# 4-Microcontroller.net
KiCad netlist of a schematic drawn in Altium Designer
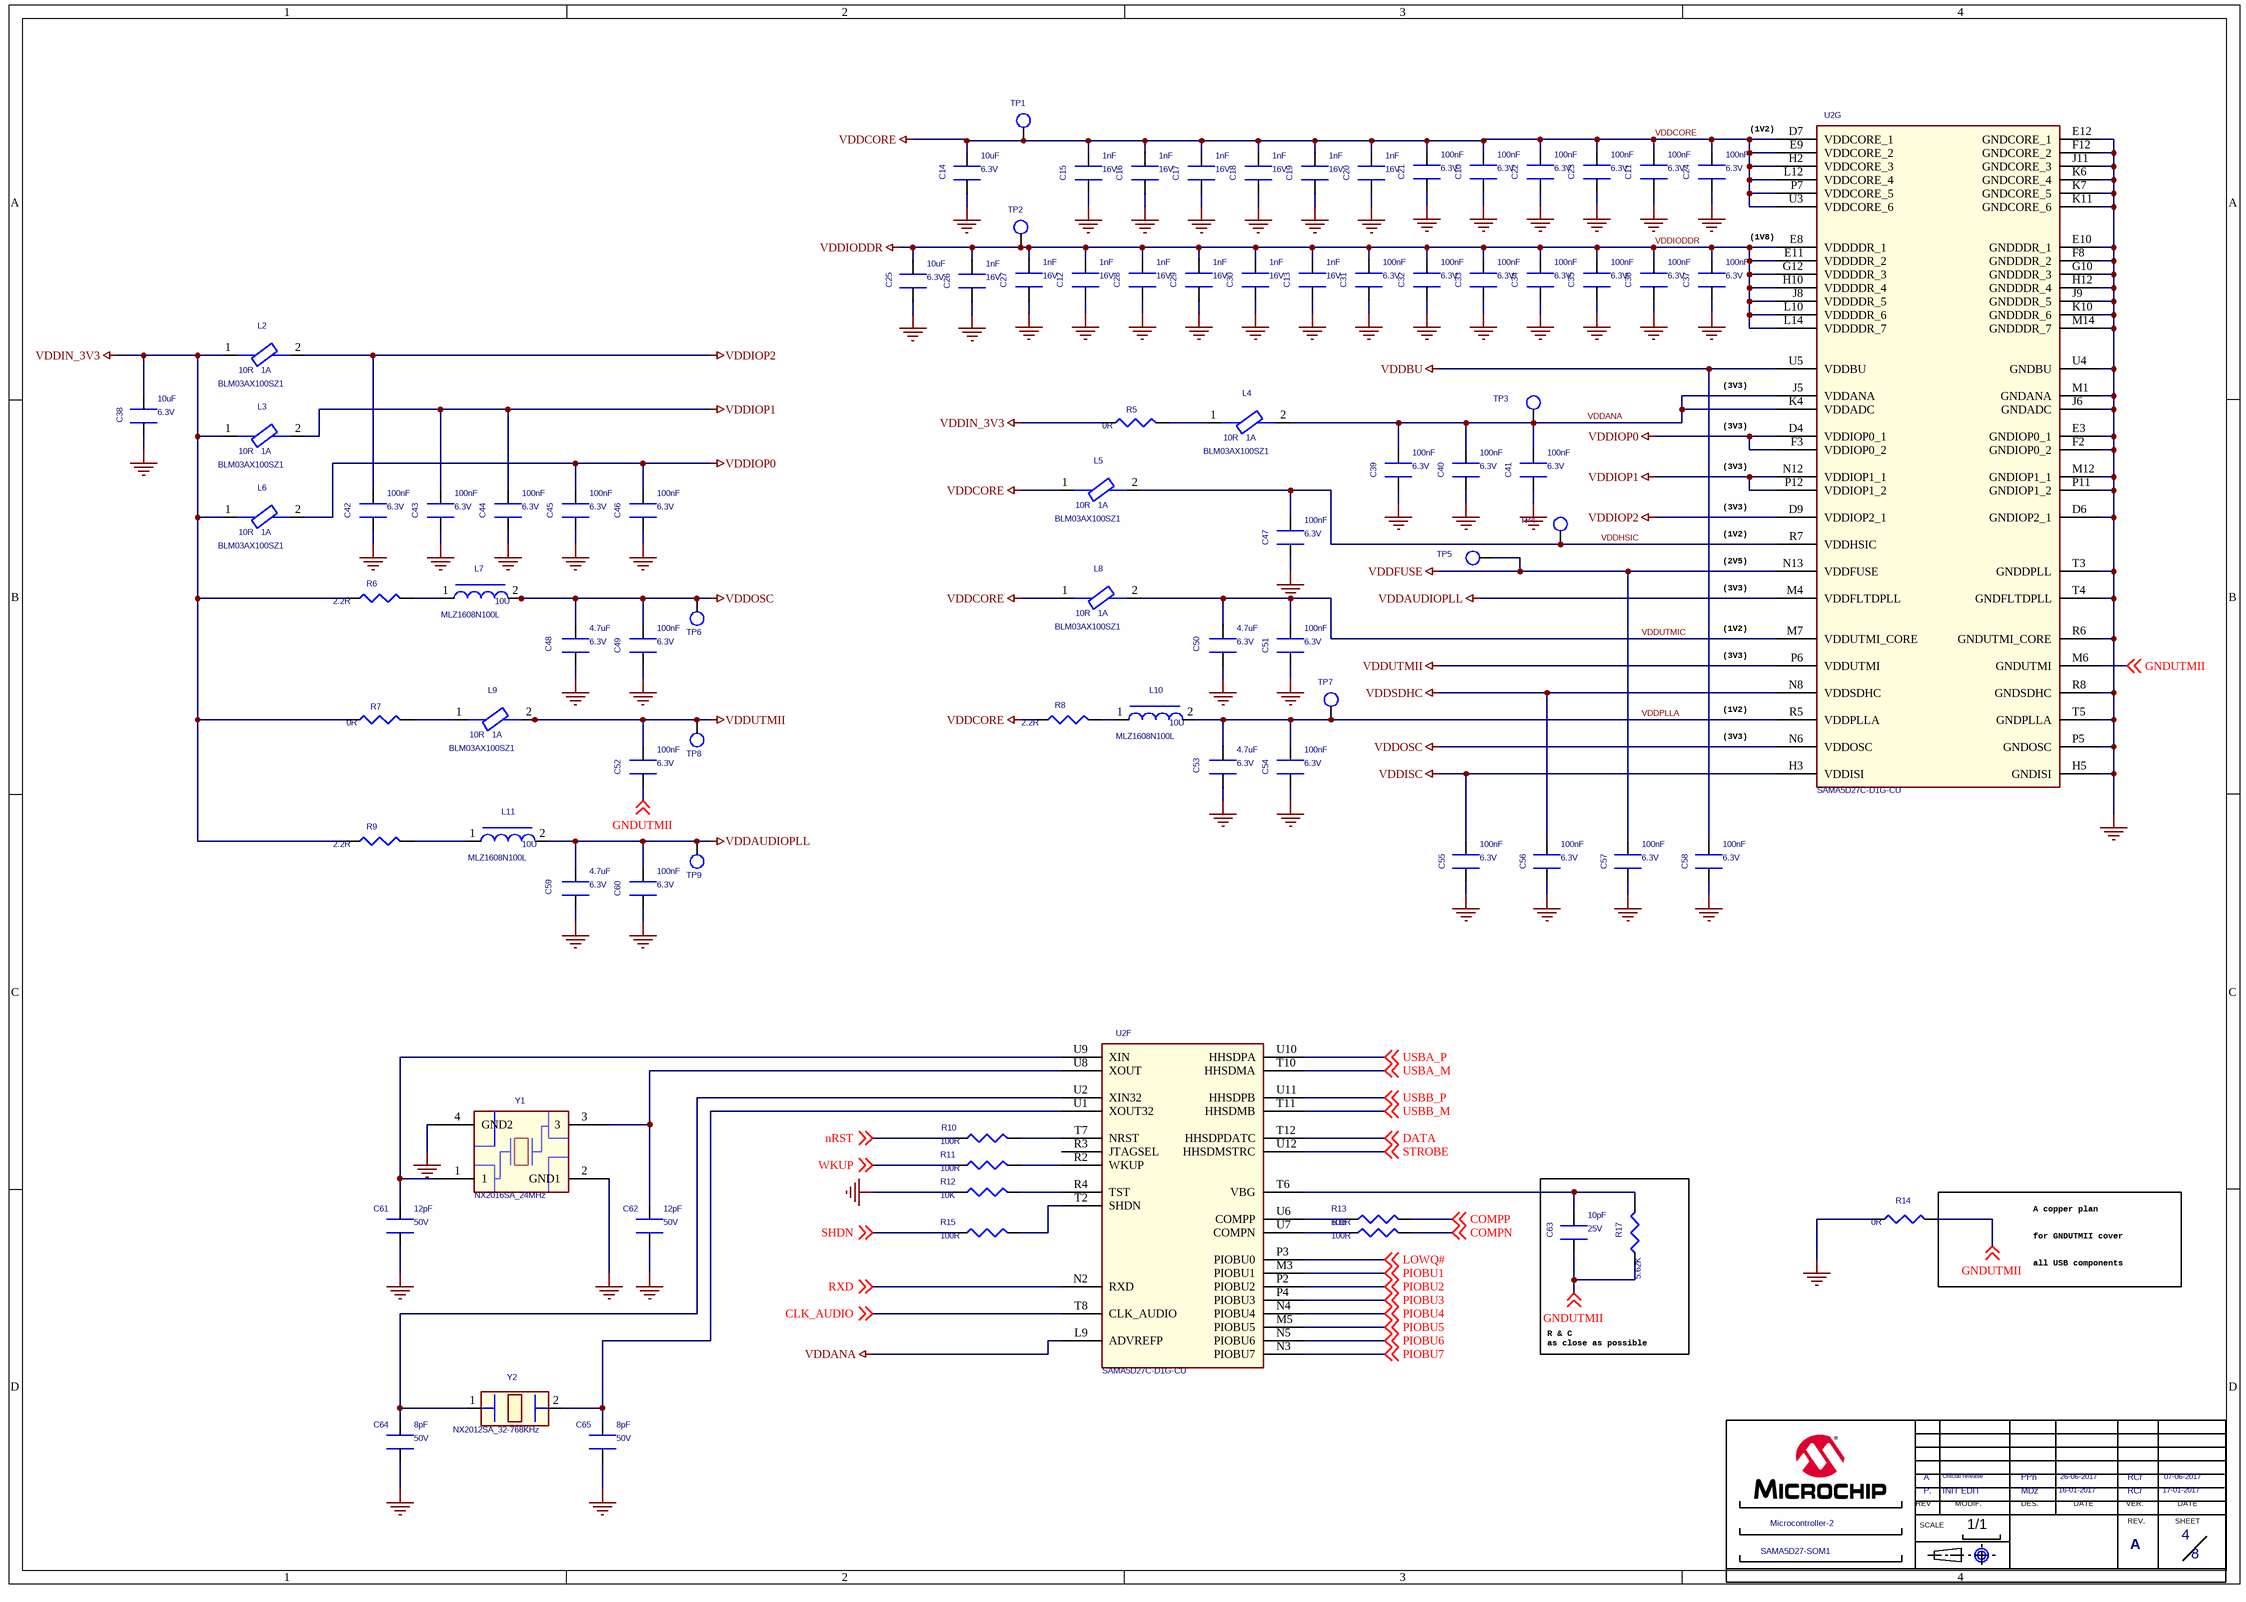
[diagram p0: 4-Microcontroller.SchDoc]

(export (version "E")
  (design (tool "Eeschema 10.0.6"))
  (components
    (comp (ref "C10")
      (value "xpF x% xV")
      (footprint "C0201")
      (fields (field (name "VALEUR") "100nF") (field (name "TENSION") "6.3V") (field (name "HAUTEUR") "xmm"))
      (libsource (lib "*") (part "C0201-100nF-X5R-6.3V"))
    )
    (comp (ref "C11")
      (value "xpF x% xV")
      (footprint "C0201")
      (fields (field (name "VALEUR") "100nF") (field (name "TENSION") "6.3V") (field (name "HAUTEUR") "xmm"))
      (libsource (lib "*") (part "C0201-100nF-X5R-6.3V"))
    )
    (comp (ref "C12")
      (value "xpF x% xV")
      (footprint "C0201")
      (fields (field (name "TENSION") "16V") (field (name "VALEUR") "1nF") (field (name "HAUTEUR") "xmm"))
      (libsource (lib "*") (part "C0201-1nF-X7R-16V-10%"))
    )
    (comp (ref "C13")
      (value "xpF x% xV")
      (footprint "C0201")
      (fields (field (name "TENSION") "16V") (field (name "VALEUR") "1nF") (field (name "HAUTEUR") "xmm"))
      (libsource (lib "*") (part "C0201-1nF-X7R-16V-10%"))
    )
    (comp (ref "C14")
      (value "xpF x% xV")
      (footprint "C0402")
      (fields (field (name "TENSION") "6.3V") (field (name "VALEUR") "10uF") (field (name "HAUTEUR") "xmm"))
      (libsource (lib "*") (part "C0402-10uF-X5R-6.3V"))
    )
    (comp (ref "C15")
      (value "xpF x% xV")
      (footprint "C0201")
      (fields (field (name "TENSION") "16V") (field (name "VALEUR") "1nF") (field (name "HAUTEUR") "xmm"))
      (libsource (lib "*") (part "C0201-1nF-X7R-16V-10%"))
    )
    (comp (ref "C16")
      (value "xpF x% xV")
      (footprint "C0201")
      (fields (field (name "TENSION") "16V") (field (name "VALEUR") "1nF") (field (name "HAUTEUR") "xmm"))
      (libsource (lib "*") (part "C0201-1nF-X7R-16V-10%"))
    )
    (comp (ref "C17")
      (value "xpF x% xV")
      (footprint "C0201")
      (fields (field (name "TENSION") "16V") (field (name "VALEUR") "1nF") (field (name "HAUTEUR") "xmm"))
      (libsource (lib "*") (part "C0201-1nF-X7R-16V-10%"))
    )
    (comp (ref "C18")
      (value "xpF x% xV")
      (footprint "C0201")
      (fields (field (name "TENSION") "16V") (field (name "VALEUR") "1nF") (field (name "HAUTEUR") "xmm"))
      (libsource (lib "*") (part "C0201-1nF-X7R-16V-10%"))
    )
    (comp (ref "C19")
      (value "xpF x% xV")
      (footprint "C0201")
      (fields (field (name "TENSION") "16V") (field (name "VALEUR") "1nF") (field (name "HAUTEUR") "xmm"))
      (libsource (lib "*") (part "C0201-1nF-X7R-16V-10%"))
    )
    (comp (ref "C20")
      (value "xpF x% xV")
      (footprint "C0201")
      (fields (field (name "TENSION") "16V") (field (name "VALEUR") "1nF") (field (name "HAUTEUR") "xmm"))
      (libsource (lib "*") (part "C0201-1nF-X7R-16V-10%"))
    )
    (comp (ref "C21")
      (value "xpF x% xV")
      (footprint "C0201")
      (fields (field (name "VALEUR") "100nF") (field (name "TENSION") "6.3V") (field (name "HAUTEUR") "xmm"))
      (libsource (lib "*") (part "C0201-100nF-X5R-6.3V"))
    )
    (comp (ref "C22")
      (value "xpF x% xV")
      (footprint "C0201")
      (fields (field (name "VALEUR") "100nF") (field (name "TENSION") "6.3V") (field (name "HAUTEUR") "xmm"))
      (libsource (lib "*") (part "C0201-100nF-X5R-6.3V"))
    )
    (comp (ref "C23")
      (value "xpF x% xV")
      (footprint "C0201")
      (fields (field (name "VALEUR") "100nF") (field (name "TENSION") "6.3V") (field (name "HAUTEUR") "xmm"))
      (libsource (lib "*") (part "C0201-100nF-X5R-6.3V"))
    )
    (comp (ref "C24")
      (value "xpF x% xV")
      (footprint "C0201")
      (fields (field (name "VALEUR") "100nF") (field (name "TENSION") "6.3V") (field (name "HAUTEUR") "xmm"))
      (libsource (lib "*") (part "C0201-100nF-X5R-6.3V"))
    )
    (comp (ref "C25")
      (value "xpF x% xV")
      (footprint "C0402")
      (fields (field (name "TENSION") "6.3V") (field (name "VALEUR") "10uF") (field (name "HAUTEUR") "xmm"))
      (libsource (lib "*") (part "C0402-10uF-X5R-6.3V"))
    )
    (comp (ref "C26")
      (value "xpF x% xV")
      (footprint "C0201")
      (fields (field (name "TENSION") "16V") (field (name "VALEUR") "1nF") (field (name "HAUTEUR") "xmm"))
      (libsource (lib "*") (part "C0201-1nF-X7R-16V-10%"))
    )
    (comp (ref "C27")
      (value "xpF x% xV")
      (footprint "C0201")
      (fields (field (name "TENSION") "16V") (field (name "VALEUR") "1nF") (field (name "HAUTEUR") "xmm"))
      (libsource (lib "*") (part "C0201-1nF-X7R-16V-10%"))
    )
    (comp (ref "C28")
      (value "xpF x% xV")
      (footprint "C0201")
      (fields (field (name "TENSION") "16V") (field (name "VALEUR") "1nF") (field (name "HAUTEUR") "xmm"))
      (libsource (lib "*") (part "C0201-1nF-X7R-16V-10%"))
    )
    (comp (ref "C29")
      (value "xpF x% xV")
      (footprint "C0201")
      (fields (field (name "TENSION") "16V") (field (name "VALEUR") "1nF") (field (name "HAUTEUR") "xmm"))
      (libsource (lib "*") (part "C0201-1nF-X7R-16V-10%"))
    )
    (comp (ref "C30")
      (value "xpF x% xV")
      (footprint "C0201")
      (fields (field (name "TENSION") "16V") (field (name "VALEUR") "1nF") (field (name "HAUTEUR") "xmm"))
      (libsource (lib "*") (part "C0201-1nF-X7R-16V-10%"))
    )
    (comp (ref "C31")
      (value "xpF x% xV")
      (footprint "C0201")
      (fields (field (name "VALEUR") "100nF") (field (name "TENSION") "6.3V") (field (name "HAUTEUR") "xmm"))
      (libsource (lib "*") (part "C0201-100nF-X5R-6.3V"))
    )
    (comp (ref "C32")
      (value "xpF x% xV")
      (footprint "C0201")
      (fields (field (name "VALEUR") "100nF") (field (name "TENSION") "6.3V") (field (name "HAUTEUR") "xmm"))
      (libsource (lib "*") (part "C0201-100nF-X5R-6.3V"))
    )
    (comp (ref "C33")
      (value "xpF x% xV")
      (footprint "C0201")
      (fields (field (name "VALEUR") "100nF") (field (name "TENSION") "6.3V") (field (name "HAUTEUR") "xmm"))
      (libsource (lib "*") (part "C0201-100nF-X5R-6.3V"))
    )
    (comp (ref "C34")
      (value "xpF x% xV")
      (footprint "C0201")
      (fields (field (name "VALEUR") "100nF") (field (name "TENSION") "6.3V") (field (name "HAUTEUR") "xmm"))
      (libsource (lib "*") (part "C0201-100nF-X5R-6.3V"))
    )
    (comp (ref "C35")
      (value "xpF x% xV")
      (footprint "C0201")
      (fields (field (name "VALEUR") "100nF") (field (name "TENSION") "6.3V") (field (name "HAUTEUR") "xmm"))
      (libsource (lib "*") (part "C0201-100nF-X5R-6.3V"))
    )
    (comp (ref "C36")
      (value "xpF x% xV")
      (footprint "C0201")
      (fields (field (name "VALEUR") "100nF") (field (name "TENSION") "6.3V") (field (name "HAUTEUR") "xmm"))
      (libsource (lib "*") (part "C0201-100nF-X5R-6.3V"))
    )
    (comp (ref "C37")
      (value "xpF x% xV")
      (footprint "C0201")
      (fields (field (name "VALEUR") "100nF") (field (name "TENSION") "6.3V") (field (name "HAUTEUR") "xmm"))
      (libsource (lib "*") (part "C0201-100nF-X5R-6.3V"))
    )
    (comp (ref "C38")
      (value "xpF x% xV")
      (footprint "C0402")
      (fields (field (name "TENSION") "6.3V") (field (name "VALEUR") "10uF") (field (name "HAUTEUR") "xmm"))
      (libsource (lib "*") (part "C0402-10uF-X5R-6.3V"))
    )
    (comp (ref "C39")
      (value "xpF x% xV")
      (footprint "C0201")
      (fields (field (name "VALEUR") "100nF") (field (name "TENSION") "6.3V") (field (name "HAUTEUR") "xmm"))
      (libsource (lib "*") (part "C0201-100nF-X5R-6.3V"))
    )
    (comp (ref "C40")
      (value "xpF x% xV")
      (footprint "C0201")
      (fields (field (name "VALEUR") "100nF") (field (name "TENSION") "6.3V") (field (name "HAUTEUR") "xmm"))
      (libsource (lib "*") (part "C0201-100nF-X5R-6.3V"))
    )
    (comp (ref "C41")
      (value "xpF x% xV")
      (footprint "C0201")
      (fields (field (name "VALEUR") "100nF") (field (name "TENSION") "6.3V") (field (name "HAUTEUR") "xmm"))
      (libsource (lib "*") (part "C0201-100nF-X5R-6.3V"))
    )
    (comp (ref "C42")
      (value "xpF x% xV")
      (footprint "C0201")
      (fields (field (name "VALEUR") "100nF") (field (name "TENSION") "6.3V") (field (name "HAUTEUR") "xmm"))
      (libsource (lib "*") (part "C0201-100nF-X5R-6.3V"))
    )
    (comp (ref "C43")
      (value "xpF x% xV")
      (footprint "C0201")
      (fields (field (name "VALEUR") "100nF") (field (name "TENSION") "6.3V") (field (name "HAUTEUR") "xmm"))
      (libsource (lib "*") (part "C0201-100nF-X5R-6.3V"))
    )
    (comp (ref "C44")
      (value "xpF x% xV")
      (footprint "C0201")
      (fields (field (name "VALEUR") "100nF") (field (name "TENSION") "6.3V") (field (name "HAUTEUR") "xmm"))
      (libsource (lib "*") (part "C0201-100nF-X5R-6.3V"))
    )
    (comp (ref "C45")
      (value "xpF x% xV")
      (footprint "C0201")
      (fields (field (name "VALEUR") "100nF") (field (name "TENSION") "6.3V") (field (name "HAUTEUR") "xmm"))
      (libsource (lib "*") (part "C0201-100nF-X5R-6.3V"))
    )
    (comp (ref "C46")
      (value "xpF x% xV")
      (footprint "C0201")
      (fields (field (name "VALEUR") "100nF") (field (name "TENSION") "6.3V") (field (name "HAUTEUR") "xmm"))
      (libsource (lib "*") (part "C0201-100nF-X5R-6.3V"))
    )
    (comp (ref "C47")
      (value "xpF x% xV")
      (footprint "C0201")
      (fields (field (name "VALEUR") "100nF") (field (name "TENSION") "6.3V") (field (name "HAUTEUR") "xmm"))
      (libsource (lib "*") (part "C0201-100nF-X5R-6.3V"))
    )
    (comp (ref "C48")
      (value "xpF x% xV")
      (footprint "C0402")
      (fields (field (name "TENSION") "6.3V") (field (name "VALEUR") "4.7uF") (field (name "HAUTEUR") "xmm"))
      (libsource (lib "*") (part "C0402-4.7uF-X5R-6.3V-10%"))
    )
    (comp (ref "C49")
      (value "xpF x% xV")
      (footprint "C0201")
      (fields (field (name "VALEUR") "100nF") (field (name "TENSION") "6.3V") (field (name "HAUTEUR") "xmm"))
      (libsource (lib "*") (part "C0201-100nF-X5R-6.3V"))
    )
    (comp (ref "C50")
      (value "xpF x% xV")
      (footprint "C0402")
      (fields (field (name "TENSION") "6.3V") (field (name "VALEUR") "4.7uF") (field (name "HAUTEUR") "xmm"))
      (libsource (lib "*") (part "C0402-4.7uF-X5R-6.3V-10%"))
    )
    (comp (ref "C51")
      (value "xpF x% xV")
      (footprint "C0201")
      (fields (field (name "VALEUR") "100nF") (field (name "TENSION") "6.3V") (field (name "HAUTEUR") "xmm"))
      (libsource (lib "*") (part "C0201-100nF-X5R-6.3V"))
    )
    (comp (ref "C52")
      (value "xpF x% xV")
      (footprint "C0201")
      (fields (field (name "VALEUR") "100nF") (field (name "TENSION") "6.3V") (field (name "HAUTEUR") "xmm"))
      (libsource (lib "*") (part "C0201-100nF-X5R-6.3V"))
    )
    (comp (ref "C53")
      (value "xpF x% xV")
      (footprint "C0402")
      (fields (field (name "TENSION") "6.3V") (field (name "VALEUR") "4.7uF") (field (name "HAUTEUR") "xmm"))
      (libsource (lib "*") (part "C0402-4.7uF-X5R-6.3V-10%"))
    )
    (comp (ref "C54")
      (value "xpF x% xV")
      (footprint "C0201")
      (fields (field (name "VALEUR") "100nF") (field (name "TENSION") "6.3V") (field (name "HAUTEUR") "xmm"))
      (libsource (lib "*") (part "C0201-100nF-X5R-6.3V"))
    )
    (comp (ref "C55")
      (value "xpF x% xV")
      (footprint "C0201")
      (fields (field (name "VALEUR") "100nF") (field (name "TENSION") "6.3V") (field (name "HAUTEUR") "xmm"))
      (libsource (lib "*") (part "C0201-100nF-X5R-6.3V"))
    )
    (comp (ref "C56")
      (value "xpF x% xV")
      (footprint "C0201")
      (fields (field (name "VALEUR") "100nF") (field (name "TENSION") "6.3V") (field (name "HAUTEUR") "xmm"))
      (libsource (lib "*") (part "C0201-100nF-X5R-6.3V"))
    )
    (comp (ref "C57")
      (value "xpF x% xV")
      (footprint "C0201")
      (fields (field (name "VALEUR") "100nF") (field (name "TENSION") "6.3V") (field (name "HAUTEUR") "xmm"))
      (libsource (lib "*") (part "C0201-100nF-X5R-6.3V"))
    )
    (comp (ref "C58")
      (value "xpF x% xV")
      (footprint "C0201")
      (fields (field (name "VALEUR") "100nF") (field (name "TENSION") "6.3V") (field (name "HAUTEUR") "xmm"))
      (libsource (lib "*") (part "C0201-100nF-X5R-6.3V"))
    )
    (comp (ref "C59")
      (value "xpF x% xV")
      (footprint "C0402")
      (fields (field (name "TENSION") "6.3V") (field (name "VALEUR") "4.7uF") (field (name "HAUTEUR") "xmm"))
      (libsource (lib "*") (part "C0402-4.7uF-X5R-6.3V-10%"))
    )
    (comp (ref "C60")
      (value "xpF x% xV")
      (footprint "C0201")
      (fields (field (name "VALEUR") "100nF") (field (name "TENSION") "6.3V") (field (name "HAUTEUR") "xmm"))
      (libsource (lib "*") (part "C0201-100nF-X5R-6.3V"))
    )
    (comp (ref "C61")
      (value "xpF x% xV")
      (footprint "C0201")
      (fields (field (name "TENSION") "50V") (field (name "VALEUR") "12pF") (field (name "HAUTEUR") "xmm"))
      (libsource (lib "*") (part "C0201-12pF-C0G-50V"))
    )
    (comp (ref "C62")
      (value "xpF x% xV")
      (footprint "C0201")
      (fields (field (name "TENSION") "50V") (field (name "VALEUR") "12pF") (field (name "HAUTEUR") "xmm"))
      (libsource (lib "*") (part "C0201-12pF-C0G-50V"))
    )
    (comp (ref "C63")
      (value "xpF x% xV")
      (footprint "C0201")
      (fields (field (name "VALEUR") "10pF") (field (name "TENSION") "25V") (field (name "HAUTEUR") "xmm"))
      (libsource (lib "*") (part "C0201-10pF-C0G-25V"))
    )
    (comp (ref "C64")
      (value "xpF x% xV")
      (footprint "C0201")
      (fields (field (name "VALEUR") "8pF") (field (name "TENSION") "50V") (field (name "HAUTEUR") "xmm"))
      (libsource (lib "*") (part "C0201-8pF-C0G-50V"))
    )
    (comp (ref "C65")
      (value "xpF x% xV")
      (footprint "C0201")
      (fields (field (name "VALEUR") "8pF") (field (name "TENSION") "50V") (field (name "HAUTEUR") "xmm"))
      (libsource (lib "*") (part "C0201-8pF-C0G-50V"))
    )
    (comp (ref "L2")
      (value "10R   1A")
      (footprint "L0201")
      (fields
        (field (name "VALEUR") "BLM03AX100SZ1")
        (field (name "PARTNUMBER") "BLM03AX100SZ1")
        (field (name "TOLERANCE") "20%")
      )
      (libsource (lib "*") (part "BLM03AX100SZ1"))
    )
    (comp (ref "L3")
      (value "10R   1A")
      (footprint "L0201")
      (fields
        (field (name "VALEUR") "BLM03AX100SZ1")
        (field (name "PARTNUMBER") "BLM03AX100SZ1")
        (field (name "TOLERANCE") "20%")
      )
      (libsource (lib "*") (part "BLM03AX100SZ1"))
    )
    (comp (ref "L4")
      (value "10R   1A")
      (footprint "L0201")
      (fields
        (field (name "VALEUR") "BLM03AX100SZ1")
        (field (name "PARTNUMBER") "BLM03AX100SZ1")
        (field (name "TOLERANCE") "20%")
      )
      (libsource (lib "*") (part "BLM03AX100SZ1"))
    )
    (comp (ref "L5")
      (value "10R   1A")
      (footprint "L0201")
      (fields
        (field (name "VALEUR") "BLM03AX100SZ1")
        (field (name "PARTNUMBER") "BLM03AX100SZ1")
        (field (name "TOLERANCE") "20%")
      )
      (libsource (lib "*") (part "BLM03AX100SZ1"))
    )
    (comp (ref "L6")
      (value "10R   1A")
      (footprint "L0201")
      (fields
        (field (name "VALEUR") "BLM03AX100SZ1")
        (field (name "PARTNUMBER") "BLM03AX100SZ1")
        (field (name "TOLERANCE") "20%")
      )
      (libsource (lib "*") (part "BLM03AX100SZ1"))
    )
    (comp (ref "L7")
      (value "10U")
      (footprint "L0603_02")
      (fields
        (field (name "VALEUR") "MLZ1608N100L")
        (field (name "PARTNUMBER") "MLZ1608N100L")
        (field (name "TOLERANCE") "20%")
      )
      (libsource (lib "*") (part "MLZ1608N100L"))
    )
    (comp (ref "L8")
      (value "10R   1A")
      (footprint "L0201")
      (fields
        (field (name "VALEUR") "BLM03AX100SZ1")
        (field (name "PARTNUMBER") "BLM03AX100SZ1")
        (field (name "TOLERANCE") "20%")
      )
      (libsource (lib "*") (part "BLM03AX100SZ1"))
    )
    (comp (ref "L9")
      (value "10R   1A")
      (footprint "L0201")
      (fields
        (field (name "VALEUR") "BLM03AX100SZ1")
        (field (name "PARTNUMBER") "BLM03AX100SZ1")
        (field (name "TOLERANCE") "20%")
      )
      (libsource (lib "*") (part "BLM03AX100SZ1"))
    )
    (comp (ref "L10")
      (value "10U")
      (footprint "L0603_02")
      (fields
        (field (name "VALEUR") "MLZ1608N100L")
        (field (name "PARTNUMBER") "MLZ1608N100L")
        (field (name "TOLERANCE") "20%")
      )
      (libsource (lib "*") (part "MLZ1608N100L"))
    )
    (comp (ref "L11")
      (value "10U")
      (footprint "L0603_02")
      (fields
        (field (name "VALEUR") "MLZ1608N100L")
        (field (name "PARTNUMBER") "MLZ1608N100L")
        (field (name "TOLERANCE") "20%")
      )
      (libsource (lib "*") (part "MLZ1608N100L"))
    )
    (comp (ref "R5")
      (value "xR x% xW")
      (footprint "R0201")
      (fields (field (name "VALEUR") "0R") (field (name "TOLERANCE") "x%"))
      (libsource (lib "*") (part "R0201-0R"))
    )
    (comp (ref "R6")
      (value "xR x% xW")
      (footprint "R0201")
      (fields (field (name "TOLERANCE") "5%") (field (name "VALEUR") "2.2R"))
      (libsource (lib "*") (part "R0201-2.2R-5%"))
    )
    (comp (ref "R7")
      (value "xR x% xW")
      (footprint "R0201")
      (fields (field (name "VALEUR") "0R") (field (name "TOLERANCE") "x%"))
      (libsource (lib "*") (part "R0201-0R"))
    )
    (comp (ref "R8")
      (value "xR x% xW")
      (footprint "R0201")
      (fields (field (name "TOLERANCE") "5%") (field (name "VALEUR") "2.2R"))
      (libsource (lib "*") (part "R0201-2.2R-5%"))
    )
    (comp (ref "R9")
      (value "xR x% xW")
      (footprint "R0201")
      (fields (field (name "TOLERANCE") "5%") (field (name "VALEUR") "2.2R"))
      (libsource (lib "*") (part "R0201-2.2R-5%"))
    )
    (comp (ref "R10")
      (value "xR x% xW")
      (footprint "R0201")
      (fields (field (name "VALEUR") "100R") (field (name "TOLERANCE") "5%"))
      (libsource (lib "*") (part "R0201-100R-5%"))
    )
    (comp (ref "R11")
      (value "xR x% xW")
      (footprint "R0201")
      (fields (field (name "VALEUR") "100R") (field (name "TOLERANCE") "5%"))
      (libsource (lib "*") (part "R0201-100R-5%"))
    )
    (comp (ref "R12")
      (value "xR x% xW")
      (footprint "R0201")
      (fields (field (name "VALEUR") "10K") (field (name "TOLERANCE") "5%"))
      (libsource (lib "*") (part "R0201-10K-5%"))
    )
    (comp (ref "R13")
      (value "xR x% xW")
      (footprint "R0201")
      (fields (field (name "TOLERANCE") "1%") (field (name "VALEUR") "100R"))
      (libsource (lib "*") (part "R0201-100R-1%"))
    )
    (comp (ref "R14")
      (value "xR x% xW")
      (footprint "R0402")
      (fields (field (name "VALEUR") "0R") (field (name "TOLERANCE") "x%"))
      (libsource (lib "*") (part "R0402-0R"))
    )
    (comp (ref "R15")
      (value "xR x% xW")
      (footprint "R0201")
      (fields (field (name "VALEUR") "100R") (field (name "TOLERANCE") "5%"))
      (libsource (lib "*") (part "R0201-100R-5%"))
    )
    (comp (ref "R16")
      (value "xR x% xW")
      (footprint "R0201")
      (fields (field (name "TOLERANCE") "1%") (field (name "VALEUR") "100R"))
      (libsource (lib "*") (part "R0201-100R-1%"))
    )
    (comp (ref "R17")
      (value "xR x% xW")
      (footprint "R0201")
      (fields (field (name "VALEUR") "5.62K") (field (name "TOLERANCE") "1%"))
      (libsource (lib "*") (part "R0201-5.62K-1%"))
    )
    (comp (ref "TP1") (value "TP") (footprint "tp-cmsrond-1mm_02") (libsource (lib "*") (part "TP")))
    (comp (ref "TP2") (value "TP") (footprint "tp-cmsrond-1mm_02") (libsource (lib "*") (part "TP")))
    (comp (ref "TP3") (value "TP") (footprint "tp-cmsrond-1mm_02") (libsource (lib "*") (part "TP")))
    (comp (ref "TP4") (value "TP") (footprint "tp-cmsrond-1mm_02") (libsource (lib "*") (part "TP")))
    (comp (ref "TP5") (value "TP") (footprint "tp-cmsrond-1mm_02") (libsource (lib "*") (part "TP")))
    (comp (ref "TP6") (value "TP") (footprint "tp-cmsrond-1mm_02") (libsource (lib "*") (part "TP")))
    (comp (ref "TP7") (value "TP") (footprint "tp-cmsrond-1mm_02") (libsource (lib "*") (part "TP")))
    (comp (ref "TP8") (value "TP") (footprint "tp-cmsrond-1mm_02") (libsource (lib "*") (part "TP")))
    (comp (ref "TP9") (value "TP") (footprint "tp-cmsrond-1mm_02") (libsource (lib "*") (part "TP")))
    (comp (ref "U2")
      (value "SAMA5D27C-D1G-CU")
      (footprint "BGA289_02")
      (libsource (lib "*") (part "SAMA5D27C-D1G-CU"))
    )
    (comp (ref "Y1")
      (value "NX2016SA_24MHz")
      (footprint "QUARTZ-NX2016SA_01")
      (libsource (lib "*") (part "NX2016SA_24MHz"))
    )
    (comp (ref "Y2")
      (value "NX2012SA_32-768KHz")
      (footprint "QUARTZ-NX2012SA_01")
      (libsource (lib "*") (part "NX2012SA_32-768KHz"))
    )
  )
  (nets
    (net (code "1") (name "/VDDHSIC") (class "Default")
      (node (ref "C47") (pin "2") (pinfunction "2_2") (pintype "passive"))
      (node (ref "L5") (pin "2") (pinfunction "2_2") (pintype "passive"))
      (node (ref "TP4") (pin "1") (pinfunction "1_1") (pintype "passive"))
      (node (ref "U2") (pin "R7") (pinfunction "VDDHSIC_R7") (pintype "passive"))
    )
    (net (code "2") (name "/VDDPLLA") (class "Default")
      (node (ref "C53") (pin "2") (pinfunction "2_2") (pintype "passive"))
      (node (ref "C54") (pin "2") (pinfunction "2_2") (pintype "passive"))
      (node (ref "L10") (pin "2") (pinfunction "2_2") (pintype "passive"))
      (node (ref "TP7") (pin "1") (pinfunction "1_1") (pintype "passive"))
      (node (ref "U2") (pin "R5") (pinfunction "VDDPLLA_R5") (pintype "passive"))
    )
    (net (code "3") (name "/VDDUTMIC") (class "Default")
      (node (ref "C50") (pin "2") (pinfunction "2_2") (pintype "passive"))
      (node (ref "C51") (pin "2") (pinfunction "2_2") (pintype "passive"))
      (node (ref "L8") (pin "2") (pinfunction "2_2") (pintype "passive"))
      (node (ref "U2") (pin "M7") (pinfunction "VDDUTMI_CORE_M7") (pintype "passive"))
    )
    (net (code "4") (name "CLK_AUDIO") (class "Default")
      (node (ref "U2") (pin "T8") (pinfunction "CLK_AUDIO_T8") (pintype "passive"))
    )
    (net (code "5") (name "COMPN") (class "Default")
      (node (ref "R16") (pin "2") (pinfunction "2_2") (pintype "passive"))
    )
    (net (code "6") (name "COMPP") (class "Default")
      (node (ref "R13") (pin "2") (pinfunction "2_2") (pintype "passive"))
    )
    (net (code "7") (name "DATA") (class "Default")
      (node (ref "U2") (pin "T12") (pinfunction "HHSDPDATC_T12") (pintype "passive"))
    )
    (net (code "8") (name "GND") (class "Default")
      (node (ref "C10") (pin "1") (pinfunction "1_1") (pintype "passive"))
      (node (ref "C11") (pin "1") (pinfunction "1_1") (pintype "passive"))
      (node (ref "C12") (pin "1") (pinfunction "1_1") (pintype "passive"))
      (node (ref "C13") (pin "1") (pinfunction "1_1") (pintype "passive"))
      (node (ref "C14") (pin "1") (pinfunction "1_1") (pintype "passive"))
      (node (ref "C15") (pin "1") (pinfunction "1_1") (pintype "passive"))
      (node (ref "C16") (pin "1") (pinfunction "1_1") (pintype "passive"))
      (node (ref "C17") (pin "1") (pinfunction "1_1") (pintype "passive"))
      (node (ref "C18") (pin "1") (pinfunction "1_1") (pintype "passive"))
      (node (ref "C19") (pin "1") (pinfunction "1_1") (pintype "passive"))
      (node (ref "C20") (pin "1") (pinfunction "1_1") (pintype "passive"))
      (node (ref "C21") (pin "1") (pinfunction "1_1") (pintype "passive"))
      (node (ref "C22") (pin "1") (pinfunction "1_1") (pintype "passive"))
      (node (ref "C23") (pin "1") (pinfunction "1_1") (pintype "passive"))
      (node (ref "C24") (pin "1") (pinfunction "1_1") (pintype "passive"))
      (node (ref "C25") (pin "1") (pinfunction "1_1") (pintype "passive"))
      (node (ref "C26") (pin "1") (pinfunction "1_1") (pintype "passive"))
      (node (ref "C27") (pin "1") (pinfunction "1_1") (pintype "passive"))
      (node (ref "C28") (pin "1") (pinfunction "1_1") (pintype "passive"))
      (node (ref "C29") (pin "1") (pinfunction "1_1") (pintype "passive"))
      (node (ref "C30") (pin "1") (pinfunction "1_1") (pintype "passive"))
      (node (ref "C31") (pin "1") (pinfunction "1_1") (pintype "passive"))
      (node (ref "C32") (pin "1") (pinfunction "1_1") (pintype "passive"))
      (node (ref "C33") (pin "1") (pinfunction "1_1") (pintype "passive"))
      (node (ref "C34") (pin "1") (pinfunction "1_1") (pintype "passive"))
      (node (ref "C35") (pin "1") (pinfunction "1_1") (pintype "passive"))
      (node (ref "C36") (pin "1") (pinfunction "1_1") (pintype "passive"))
      (node (ref "C37") (pin "1") (pinfunction "1_1") (pintype "passive"))
      (node (ref "C38") (pin "1") (pinfunction "1_1") (pintype "passive"))
      (node (ref "C39") (pin "1") (pinfunction "1_1") (pintype "passive"))
      (node (ref "C40") (pin "1") (pinfunction "1_1") (pintype "passive"))
      (node (ref "C41") (pin "1") (pinfunction "1_1") (pintype "passive"))
      (node (ref "C42") (pin "1") (pinfunction "1_1") (pintype "passive"))
      (node (ref "C43") (pin "1") (pinfunction "1_1") (pintype "passive"))
      (node (ref "C44") (pin "1") (pinfunction "1_1") (pintype "passive"))
      (node (ref "C45") (pin "1") (pinfunction "1_1") (pintype "passive"))
      (node (ref "C46") (pin "1") (pinfunction "1_1") (pintype "passive"))
      (node (ref "C47") (pin "1") (pinfunction "1_1") (pintype "passive"))
      (node (ref "C48") (pin "1") (pinfunction "1_1") (pintype "passive"))
      (node (ref "C49") (pin "1") (pinfunction "1_1") (pintype "passive"))
      (node (ref "C50") (pin "1") (pinfunction "1_1") (pintype "passive"))
      (node (ref "C51") (pin "1") (pinfunction "1_1") (pintype "passive"))
      (node (ref "C53") (pin "1") (pinfunction "1_1") (pintype "passive"))
      (node (ref "C54") (pin "1") (pinfunction "1_1") (pintype "passive"))
      (node (ref "C55") (pin "1") (pinfunction "1_1") (pintype "passive"))
      (node (ref "C56") (pin "1") (pinfunction "1_1") (pintype "passive"))
      (node (ref "C57") (pin "1") (pinfunction "1_1") (pintype "passive"))
      (node (ref "C58") (pin "1") (pinfunction "1_1") (pintype "passive"))
      (node (ref "C59") (pin "1") (pinfunction "1_1") (pintype "passive"))
      (node (ref "C60") (pin "1") (pinfunction "1_1") (pintype "passive"))
      (node (ref "C61") (pin "1") (pinfunction "1_1") (pintype "passive"))
      (node (ref "C62") (pin "1") (pinfunction "1_1") (pintype "passive"))
      (node (ref "C64") (pin "1") (pinfunction "1_1") (pintype "passive"))
      (node (ref "C65") (pin "1") (pinfunction "1_1") (pintype "passive"))
      (node (ref "R12") (pin "1") (pinfunction "1_1") (pintype "passive"))
      (node (ref "R14") (pin "1") (pinfunction "1_1") (pintype "passive"))
      (node (ref "U2") (pin "D6") (pinfunction "GNDIOP2_1_D6") (pintype "passive"))
      (node (ref "U2") (pin "E10") (pinfunction "GNDDDR_1_E10") (pintype "passive"))
      (node (ref "U2") (pin "E12") (pinfunction "GNDCORE_1_E12") (pintype "passive"))
      (node (ref "U2") (pin "E3") (pinfunction "GNDIOP0_1_E3") (pintype "passive"))
      (node (ref "U2") (pin "F12") (pinfunction "GNDCORE_2_F12") (pintype "passive"))
      (node (ref "U2") (pin "F2") (pinfunction "GNDIOP0_2_F2") (pintype "passive"))
      (node (ref "U2") (pin "F8") (pinfunction "GNDDDR_2_F8") (pintype "passive"))
      (node (ref "U2") (pin "G10") (pinfunction "GNDDDR_3_G10") (pintype "passive"))
      (node (ref "U2") (pin "H12") (pinfunction "GNDDDR_4_H12") (pintype "passive"))
      (node (ref "U2") (pin "H5") (pinfunction "GNDISI_H5") (pintype "passive"))
      (node (ref "U2") (pin "J11") (pinfunction "GNDCORE_3_J11") (pintype "passive"))
      (node (ref "U2") (pin "J6") (pinfunction "GNDADC_J6") (pintype "passive"))
      (node (ref "U2") (pin "J9") (pinfunction "GNDDDR_5_J9") (pintype "passive"))
      (node (ref "U2") (pin "K10") (pinfunction "GNDDDR_6_K10") (pintype "passive"))
      (node (ref "U2") (pin "K11") (pinfunction "GNDCORE_6_K11") (pintype "passive"))
      (node (ref "U2") (pin "K6") (pinfunction "GNDCORE_4_K6") (pintype "passive"))
      (node (ref "U2") (pin "K7") (pinfunction "GNDCORE_5_K7") (pintype "passive"))
      (node (ref "U2") (pin "M1") (pinfunction "GNDANA_M1") (pintype "passive"))
      (node (ref "U2") (pin "M12") (pinfunction "GNDIOP1_1_M12") (pintype "passive"))
      (node (ref "U2") (pin "M14") (pinfunction "GNDDDR_7_M14") (pintype "passive"))
      (node (ref "U2") (pin "P11") (pinfunction "GNDIOP1_2_P11") (pintype "passive"))
      (node (ref "U2") (pin "P5") (pinfunction "GNDOSC_P5") (pintype "passive"))
      (node (ref "U2") (pin "R6") (pinfunction "GNDUTMI_CORE_R6") (pintype "passive"))
      (node (ref "U2") (pin "R8") (pinfunction "GNDSDHC_R8") (pintype "passive"))
      (node (ref "U2") (pin "T3") (pinfunction "GNDDPLL_T3") (pintype "passive"))
      (node (ref "U2") (pin "T4") (pinfunction "GNDFLTDPLL_T4") (pintype "passive"))
      (node (ref "U2") (pin "T5") (pinfunction "GNDPLLA_T5") (pintype "passive"))
      (node (ref "U2") (pin "U4") (pinfunction "GNDBU_U4") (pintype "passive"))
      (node (ref "Y1") (pin "2") (pinfunction "GND1_2") (pintype "passive"))
      (node (ref "Y1") (pin "4") (pinfunction "GND2_4") (pintype "passive"))
    )
    (net (code "9") (name "GNDUTMII") (class "Default")
      (node (ref "C52") (pin "1") (pinfunction "1_1") (pintype "passive"))
      (node (ref "C63") (pin "1") (pinfunction "1_1") (pintype "passive"))
      (node (ref "R14") (pin "2") (pinfunction "2_2") (pintype "passive"))
      (node (ref "R17") (pin "1") (pinfunction "1_1") (pintype "passive"))
      (node (ref "U2") (pin "M6") (pinfunction "GNDUTMI_M6") (pintype "passive"))
    )
    (net (code "10") (name "LOWQ#") (class "Default")
      (node (ref "U2") (pin "P3") (pinfunction "PIOBU0_P3") (pintype "passive"))
    )
    (net (code "11") (name "Net-(L4-Pad1)") (class "Default")
      (node (ref "L4") (pin "1") (pinfunction "1_1") (pintype "passive"))
      (node (ref "R5") (pin "2") (pinfunction "2_2") (pintype "passive"))
    )
    (net (code "12") (name "Net-(L7-Pad1)") (class "Default")
      (node (ref "L7") (pin "1") (pinfunction "1_1") (pintype "passive"))
      (node (ref "R6") (pin "2") (pinfunction "2_2") (pintype "passive"))
    )
    (net (code "13") (name "Net-(L9-Pad1)") (class "Default")
      (node (ref "L9") (pin "1") (pinfunction "1_1") (pintype "passive"))
      (node (ref "R7") (pin "2") (pinfunction "2_2") (pintype "passive"))
    )
    (net (code "14") (name "Net-(L10-Pad1)") (class "Default")
      (node (ref "L10") (pin "1") (pinfunction "1_1") (pintype "passive"))
      (node (ref "R8") (pin "2") (pinfunction "2_2") (pintype "passive"))
    )
    (net (code "15") (name "Net-(L11-Pad1)") (class "Default")
      (node (ref "L11") (pin "1") (pinfunction "1_1") (pintype "passive"))
      (node (ref "R9") (pin "2") (pinfunction "2_2") (pintype "passive"))
    )
    (net (code "16") (name "Net-(U2F-COMPN)") (class "Default")
      (node (ref "R16") (pin "1") (pinfunction "1_1") (pintype "passive"))
      (node (ref "U2") (pin "U7") (pinfunction "COMPN_U7") (pintype "passive"))
    )
    (net (code "17") (name "Net-(U2F-COMPP)") (class "Default")
      (node (ref "R13") (pin "1") (pinfunction "1_1") (pintype "passive"))
      (node (ref "U2") (pin "U6") (pinfunction "COMPP_U6") (pintype "passive"))
    )
    (net (code "18") (name "Net-(U2F-NRST)") (class "Default")
      (node (ref "R10") (pin "2") (pinfunction "2_2") (pintype "passive"))
      (node (ref "U2") (pin "T7") (pinfunction "NRST_T7") (pintype "passive"))
    )
    (net (code "19") (name "Net-(U2F-SHDN)") (class "Default")
      (node (ref "R15") (pin "2") (pinfunction "2_2") (pintype "passive"))
      (node (ref "U2") (pin "T2") (pinfunction "SHDN_T2") (pintype "passive"))
    )
    (net (code "20") (name "Net-(U2F-TST)") (class "Default")
      (node (ref "R12") (pin "2") (pinfunction "2_2") (pintype "passive"))
      (node (ref "U2") (pin "R4") (pinfunction "TST_R4") (pintype "passive"))
    )
    (net (code "21") (name "Net-(U2F-VBG)") (class "Default")
      (node (ref "C63") (pin "2") (pinfunction "2_2") (pintype "passive"))
      (node (ref "R17") (pin "2") (pinfunction "2_2") (pintype "passive"))
      (node (ref "U2") (pin "T6") (pinfunction "VBG_T6") (pintype "passive"))
    )
    (net (code "22") (name "Net-(U2F-WKUP)") (class "Default")
      (node (ref "R11") (pin "2") (pinfunction "2_2") (pintype "passive"))
      (node (ref "U2") (pin "R2") (pinfunction "WKUP_R2") (pintype "passive"))
    )
    (net (code "23") (name "Net-(U2F-XIN)") (class "Default")
      (node (ref "C61") (pin "2") (pinfunction "2_2") (pintype "passive"))
      (node (ref "U2") (pin "U9") (pinfunction "XIN_U9") (pintype "passive"))
      (node (ref "Y1") (pin "1") (pinfunction "1_1") (pintype "passive"))
    )
    (net (code "24") (name "Net-(U2F-XIN32)") (class "Default")
      (node (ref "C64") (pin "2") (pinfunction "2_2") (pintype "passive"))
      (node (ref "U2") (pin "U2") (pinfunction "XIN32_U2") (pintype "passive"))
      (node (ref "Y2") (pin "1") (pinfunction "1_1") (pintype "passive"))
    )
    (net (code "25") (name "Net-(U2F-XOUT)") (class "Default")
      (node (ref "C62") (pin "2") (pinfunction "2_2") (pintype "passive"))
      (node (ref "U2") (pin "U8") (pinfunction "XOUT_U8") (pintype "passive"))
      (node (ref "Y1") (pin "3") (pinfunction "3_3") (pintype "passive"))
    )
    (net (code "26") (name "Net-(U2F-XOUT32)") (class "Default")
      (node (ref "C65") (pin "2") (pinfunction "2_2") (pintype "passive"))
      (node (ref "U2") (pin "U1") (pinfunction "XOUT32_U1") (pintype "passive"))
      (node (ref "Y2") (pin "2") (pinfunction "2_2") (pintype "passive"))
    )
    (net (code "27") (name "PIOBU1") (class "Default")
      (node (ref "U2") (pin "M3") (pinfunction "PIOBU1_M3") (pintype "passive"))
    )
    (net (code "28") (name "PIOBU2") (class "Default")
      (node (ref "U2") (pin "P2") (pinfunction "PIOBU2_P2") (pintype "passive"))
    )
    (net (code "29") (name "PIOBU3") (class "Default")
      (node (ref "U2") (pin "P4") (pinfunction "PIOBU3_P4") (pintype "passive"))
    )
    (net (code "30") (name "PIOBU4") (class "Default")
      (node (ref "U2") (pin "N4") (pinfunction "PIOBU4_N4") (pintype "passive"))
    )
    (net (code "31") (name "PIOBU5") (class "Default")
      (node (ref "U2") (pin "M5") (pinfunction "PIOBU5_M5") (pintype "passive"))
    )
    (net (code "32") (name "PIOBU6") (class "Default")
      (node (ref "U2") (pin "N5") (pinfunction "PIOBU6_N5") (pintype "passive"))
    )
    (net (code "33") (name "PIOBU7") (class "Default")
      (node (ref "U2") (pin "N3") (pinfunction "PIOBU7_N3") (pintype "passive"))
    )
    (net (code "34") (name "RXD") (class "Default")
      (node (ref "U2") (pin "N2") (pinfunction "RXD_N2") (pintype "passive"))
    )
    (net (code "35") (name "SHDN") (class "Default")
      (node (ref "R15") (pin "1") (pinfunction "1_1") (pintype "passive"))
    )
    (net (code "36") (name "STROBE") (class "Default")
      (node (ref "U2") (pin "U12") (pinfunction "HHSDMSTRC_U12") (pintype "passive"))
    )
    (net (code "37") (name "USBA_M") (class "Default")
      (node (ref "U2") (pin "T10") (pinfunction "HHSDMA_T10") (pintype "passive"))
    )
    (net (code "38") (name "USBA_P") (class "Default")
      (node (ref "U2") (pin "U10") (pinfunction "HHSDPA_U10") (pintype "passive"))
    )
    (net (code "39") (name "USBB_M") (class "Default")
      (node (ref "U2") (pin "T11") (pinfunction "HHSDMB_T11") (pintype "passive"))
    )
    (net (code "40") (name "USBB_P") (class "Default")
      (node (ref "U2") (pin "U11") (pinfunction "HHSDPB_U11") (pintype "passive"))
    )
    (net (code "41") (name "VDDANA") (class "Default")
      (node (ref "C39") (pin "2") (pinfunction "2_2") (pintype "passive"))
      (node (ref "C40") (pin "2") (pinfunction "2_2") (pintype "passive"))
      (node (ref "C41") (pin "2") (pinfunction "2_2") (pintype "passive"))
      (node (ref "L4") (pin "2") (pinfunction "2_2") (pintype "passive"))
      (node (ref "TP3") (pin "1") (pinfunction "1_1") (pintype "passive"))
      (node (ref "U2") (pin "J5") (pinfunction "VDDANA_J5") (pintype "passive"))
      (node (ref "U2") (pin "K4") (pinfunction "VDDADC_K4") (pintype "passive"))
      (node (ref "U2") (pin "L9") (pinfunction "ADVREFP_L9") (pintype "passive"))
    )
    (net (code "42") (name "VDDAUDIOPLL") (class "Default")
      (node (ref "C59") (pin "2") (pinfunction "2_2") (pintype "passive"))
      (node (ref "C60") (pin "2") (pinfunction "2_2") (pintype "passive"))
      (node (ref "L11") (pin "2") (pinfunction "2_2") (pintype "passive"))
      (node (ref "TP9") (pin "1") (pinfunction "1_1") (pintype "passive"))
      (node (ref "U2") (pin "M4") (pinfunction "VDDFLTDPLL_M4") (pintype "passive"))
    )
    (net (code "43") (name "VDDBU") (class "Default")
      (node (ref "C58") (pin "2") (pinfunction "2_2") (pintype "passive"))
      (node (ref "U2") (pin "U5") (pinfunction "VDDBU_U5") (pintype "passive"))
    )
    (net (code "44") (name "VDDCORE") (class "Default")
      (node (ref "C10") (pin "2") (pinfunction "2_2") (pintype "passive"))
      (node (ref "C11") (pin "2") (pinfunction "2_2") (pintype "passive"))
      (node (ref "C14") (pin "2") (pinfunction "2_2") (pintype "passive"))
      (node (ref "C15") (pin "2") (pinfunction "2_2") (pintype "passive"))
      (node (ref "C16") (pin "2") (pinfunction "2_2") (pintype "passive"))
      (node (ref "C17") (pin "2") (pinfunction "2_2") (pintype "passive"))
      (node (ref "C18") (pin "2") (pinfunction "2_2") (pintype "passive"))
      (node (ref "C19") (pin "2") (pinfunction "2_2") (pintype "passive"))
      (node (ref "C20") (pin "2") (pinfunction "2_2") (pintype "passive"))
      (node (ref "C21") (pin "2") (pinfunction "2_2") (pintype "passive"))
      (node (ref "C22") (pin "2") (pinfunction "2_2") (pintype "passive"))
      (node (ref "C23") (pin "2") (pinfunction "2_2") (pintype "passive"))
      (node (ref "C24") (pin "2") (pinfunction "2_2") (pintype "passive"))
      (node (ref "L5") (pin "1") (pinfunction "1_1") (pintype "passive"))
      (node (ref "L8") (pin "1") (pinfunction "1_1") (pintype "passive"))
      (node (ref "R8") (pin "1") (pinfunction "1_1") (pintype "passive"))
      (node (ref "TP1") (pin "1") (pinfunction "1_1") (pintype "passive"))
      (node (ref "U2") (pin "D7") (pinfunction "VDDCORE_1_D7") (pintype "passive"))
      (node (ref "U2") (pin "E9") (pinfunction "VDDCORE_2_E9") (pintype "passive"))
      (node (ref "U2") (pin "H2") (pinfunction "VDDCORE_3_H2") (pintype "passive"))
      (node (ref "U2") (pin "L12") (pinfunction "VDDCORE_4_L12") (pintype "passive"))
      (node (ref "U2") (pin "P7") (pinfunction "VDDCORE_5_P7") (pintype "passive"))
      (node (ref "U2") (pin "U3") (pinfunction "VDDCORE_6_U3") (pintype "passive"))
    )
    (net (code "45") (name "VDDFUSE") (class "Default")
      (node (ref "C57") (pin "2") (pinfunction "2_2") (pintype "passive"))
      (node (ref "TP5") (pin "1") (pinfunction "1_1") (pintype "passive"))
      (node (ref "U2") (pin "N13") (pinfunction "VDDFUSE_N13") (pintype "passive"))
    )
    (net (code "46") (name "VDDIN_3V3") (class "Default")
      (node (ref "C38") (pin "2") (pinfunction "2_2") (pintype "passive"))
      (node (ref "L2") (pin "1") (pinfunction "1_1") (pintype "passive"))
      (node (ref "L3") (pin "1") (pinfunction "1_1") (pintype "passive"))
      (node (ref "L6") (pin "1") (pinfunction "1_1") (pintype "passive"))
      (node (ref "R5") (pin "1") (pinfunction "1_1") (pintype "passive"))
      (node (ref "R6") (pin "1") (pinfunction "1_1") (pintype "passive"))
      (node (ref "R7") (pin "1") (pinfunction "1_1") (pintype "passive"))
      (node (ref "R9") (pin "1") (pinfunction "1_1") (pintype "passive"))
    )
    (net (code "47") (name "VDDIODDR") (class "Default")
      (node (ref "C12") (pin "2") (pinfunction "2_2") (pintype "passive"))
      (node (ref "C13") (pin "2") (pinfunction "2_2") (pintype "passive"))
      (node (ref "C25") (pin "2") (pinfunction "2_2") (pintype "passive"))
      (node (ref "C26") (pin "2") (pinfunction "2_2") (pintype "passive"))
      (node (ref "C27") (pin "2") (pinfunction "2_2") (pintype "passive"))
      (node (ref "C28") (pin "2") (pinfunction "2_2") (pintype "passive"))
      (node (ref "C29") (pin "2") (pinfunction "2_2") (pintype "passive"))
      (node (ref "C30") (pin "2") (pinfunction "2_2") (pintype "passive"))
      (node (ref "C31") (pin "2") (pinfunction "2_2") (pintype "passive"))
      (node (ref "C32") (pin "2") (pinfunction "2_2") (pintype "passive"))
      (node (ref "C33") (pin "2") (pinfunction "2_2") (pintype "passive"))
      (node (ref "C34") (pin "2") (pinfunction "2_2") (pintype "passive"))
      (node (ref "C35") (pin "2") (pinfunction "2_2") (pintype "passive"))
      (node (ref "C36") (pin "2") (pinfunction "2_2") (pintype "passive"))
      (node (ref "C37") (pin "2") (pinfunction "2_2") (pintype "passive"))
      (node (ref "TP2") (pin "1") (pinfunction "1_1") (pintype "passive"))
      (node (ref "U2") (pin "E11") (pinfunction "VDDDDR_2_E11") (pintype "passive"))
      (node (ref "U2") (pin "E8") (pinfunction "VDDDDR_1_E8") (pintype "passive"))
      (node (ref "U2") (pin "G12") (pinfunction "VDDDDR_3_G12") (pintype "passive"))
      (node (ref "U2") (pin "H10") (pinfunction "VDDDDR_4_H10") (pintype "passive"))
      (node (ref "U2") (pin "J8") (pinfunction "VDDDDR_5_J8") (pintype "passive"))
      (node (ref "U2") (pin "L10") (pinfunction "VDDDDR_6_L10") (pintype "passive"))
      (node (ref "U2") (pin "L14") (pinfunction "VDDDDR_7_L14") (pintype "passive"))
    )
    (net (code "48") (name "VDDIOP0") (class "Default")
      (node (ref "C45") (pin "2") (pinfunction "2_2") (pintype "passive"))
      (node (ref "C46") (pin "2") (pinfunction "2_2") (pintype "passive"))
      (node (ref "L6") (pin "2") (pinfunction "2_2") (pintype "passive"))
      (node (ref "U2") (pin "D4") (pinfunction "VDDIOP0_1_D4") (pintype "passive"))
      (node (ref "U2") (pin "F3") (pinfunction "VDDIOP0_2_F3") (pintype "passive"))
    )
    (net (code "49") (name "VDDIOP1") (class "Default")
      (node (ref "C43") (pin "2") (pinfunction "2_2") (pintype "passive"))
      (node (ref "C44") (pin "2") (pinfunction "2_2") (pintype "passive"))
      (node (ref "L3") (pin "2") (pinfunction "2_2") (pintype "passive"))
      (node (ref "U2") (pin "N12") (pinfunction "VDDIOP1_1_N12") (pintype "passive"))
      (node (ref "U2") (pin "P12") (pinfunction "VDDIOP1_2_P12") (pintype "passive"))
    )
    (net (code "50") (name "VDDIOP2") (class "Default")
      (node (ref "C42") (pin "2") (pinfunction "2_2") (pintype "passive"))
      (node (ref "L2") (pin "2") (pinfunction "2_2") (pintype "passive"))
      (node (ref "U2") (pin "D9") (pinfunction "VDDIOP2_1_D9") (pintype "passive"))
    )
    (net (code "51") (name "VDDISC") (class "Default")
      (node (ref "C55") (pin "2") (pinfunction "2_2") (pintype "passive"))
      (node (ref "U2") (pin "H3") (pinfunction "VDDISI_H3") (pintype "passive"))
    )
    (net (code "52") (name "VDDOSC") (class "Default")
      (node (ref "C48") (pin "2") (pinfunction "2_2") (pintype "passive"))
      (node (ref "C49") (pin "2") (pinfunction "2_2") (pintype "passive"))
      (node (ref "L7") (pin "2") (pinfunction "2_2") (pintype "passive"))
      (node (ref "TP6") (pin "1") (pinfunction "1_1") (pintype "passive"))
      (node (ref "U2") (pin "N6") (pinfunction "VDDOSC_N6") (pintype "passive"))
    )
    (net (code "53") (name "VDDSDHC") (class "Default")
      (node (ref "C56") (pin "2") (pinfunction "2_2") (pintype "passive"))
      (node (ref "U2") (pin "N8") (pinfunction "VDDSDHC_N8") (pintype "passive"))
    )
    (net (code "54") (name "VDDUTMII") (class "Default")
      (node (ref "C52") (pin "2") (pinfunction "2_2") (pintype "passive"))
      (node (ref "L9") (pin "2") (pinfunction "2_2") (pintype "passive"))
      (node (ref "TP8") (pin "1") (pinfunction "1_1") (pintype "passive"))
      (node (ref "U2") (pin "P6") (pinfunction "VDDUTMI_P6") (pintype "passive"))
    )
    (net (code "55") (name "WKUP") (class "Default")
      (node (ref "R11") (pin "1") (pinfunction "1_1") (pintype "passive"))
    )
    (net (code "56") (name "nRST") (class "Default")
      (node (ref "R10") (pin "1") (pinfunction "1_1") (pintype "passive"))
    )
    (net (code "57") (name "unconnected-(U2F-JTAGSEL-PadR3)") (class "Default")
      (node (ref "U2") (pin "R3") (pinfunction "JTAGSEL_R3") (pintype "passive"))
    )
  )
)
